# e407-roll-control.net
KiCad netlist of a schematic drawn in EAGLE
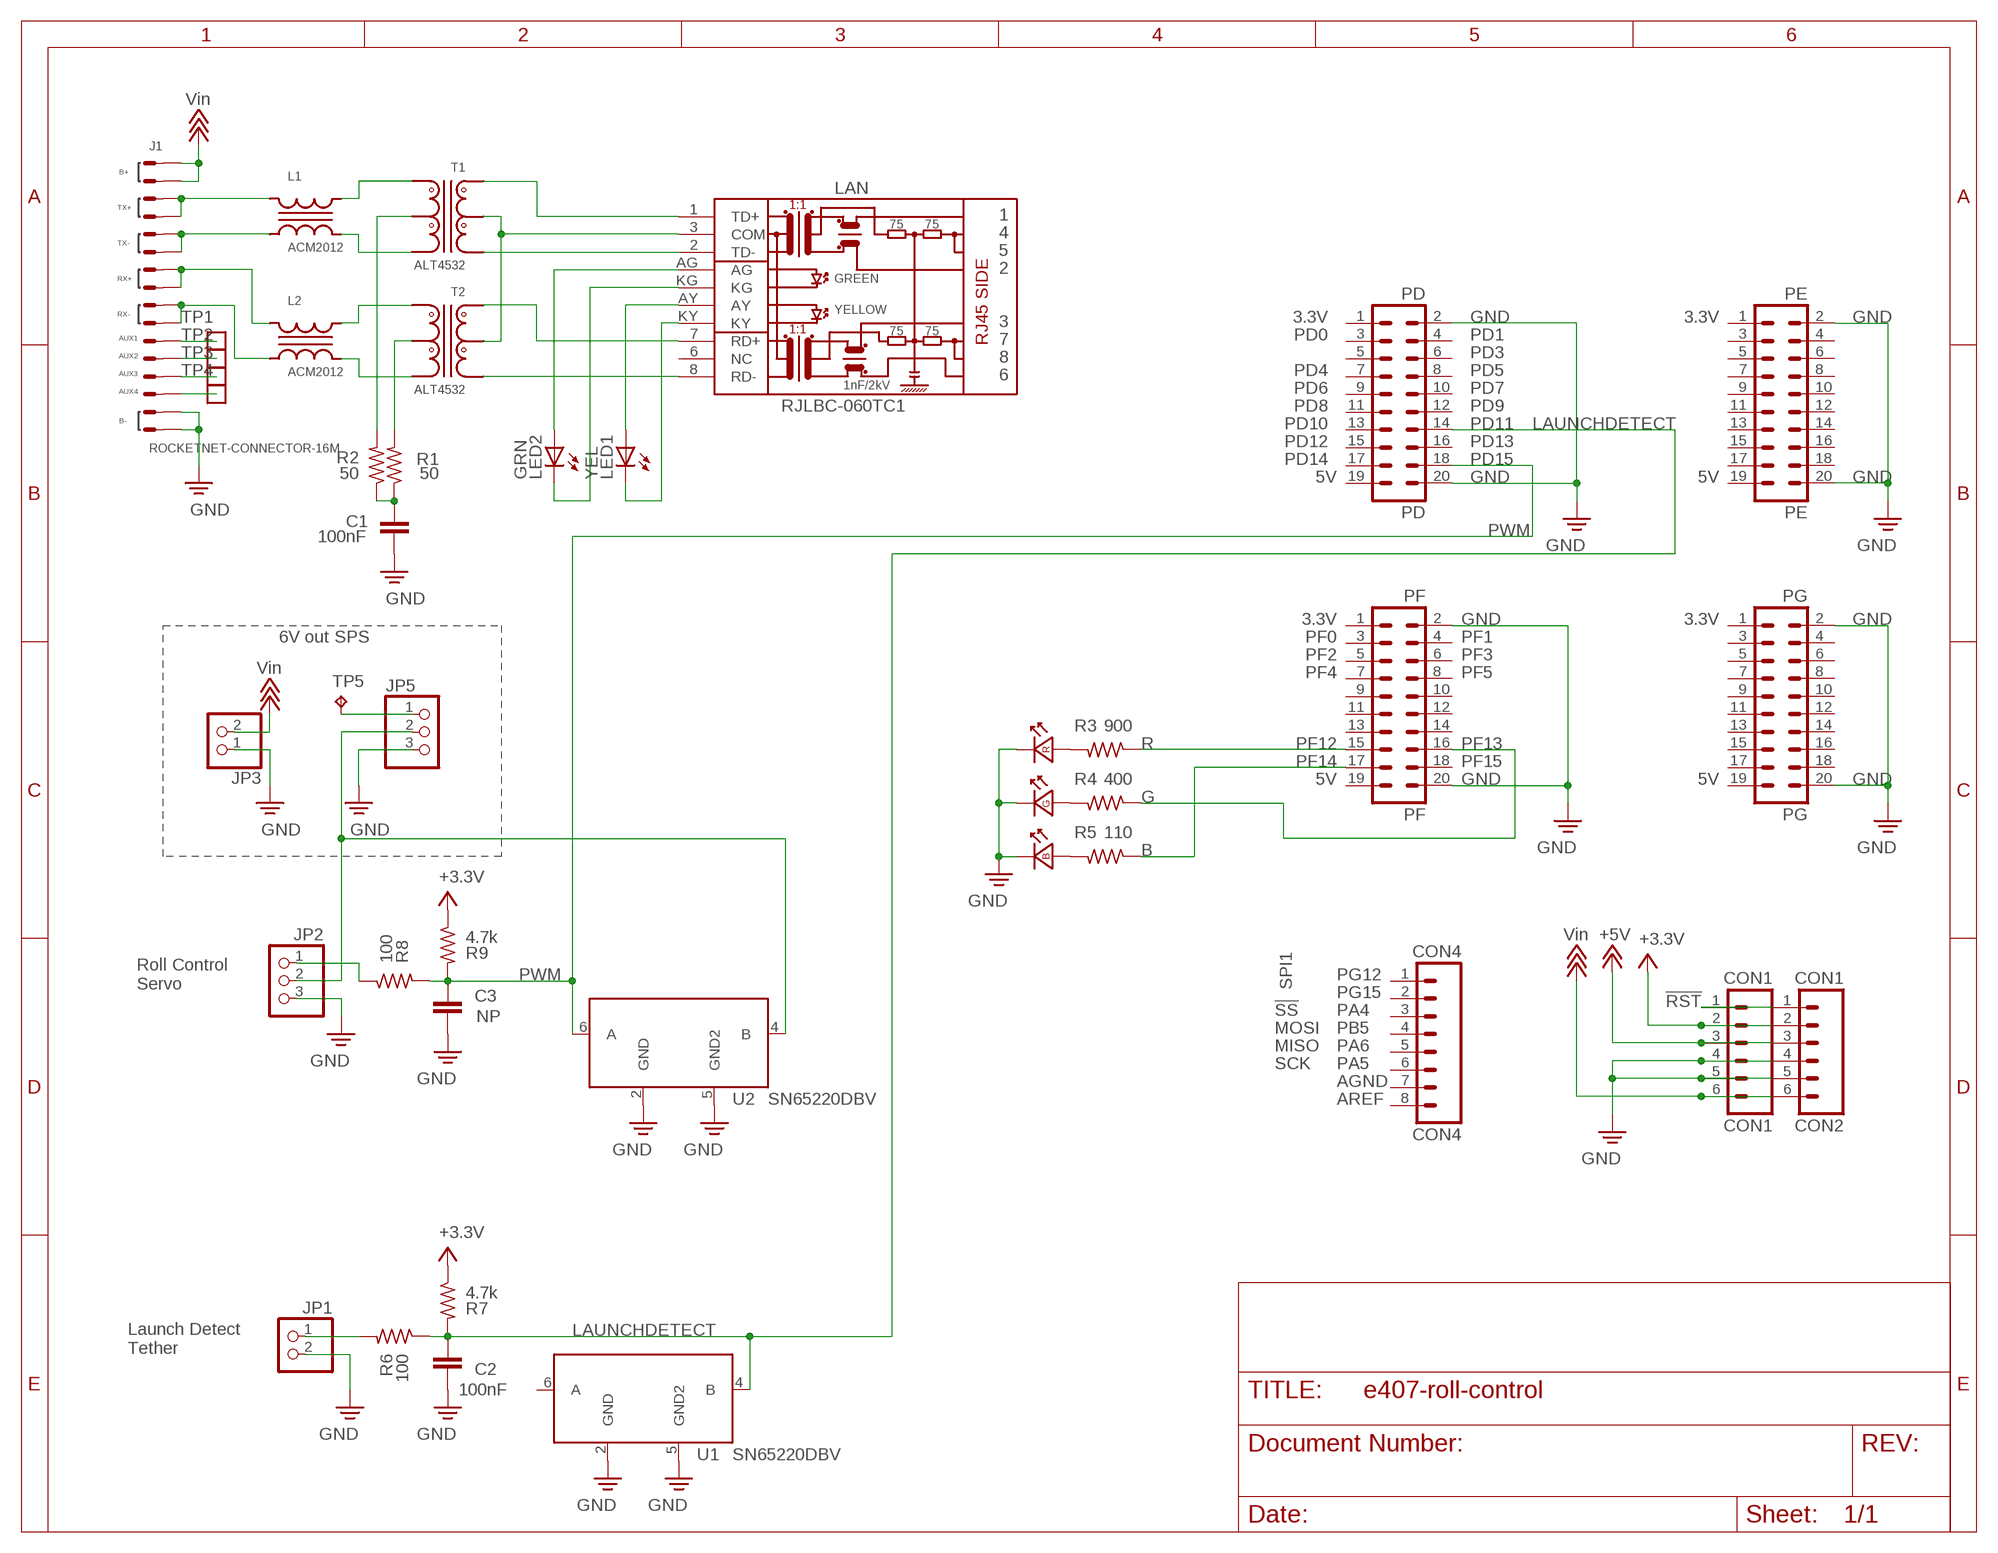
[diagram p0: schematic, sheet 1]

(export (version "E")
  (design (tool "Eeschema 10.0.6"))
  (components
    (comp (ref "C1")
      (value "100nF")
      (footprint "eagle-import:0603-B-NOSILK")
      (libsource (lib "eagle-import") (part "C-EU0603-B-NOSILK"))
    )
    (comp (ref "C2")
      (value "100nF")
      (footprint "eagle-import:0603-B-NOSILK")
      (libsource (lib "eagle-import") (part "C-EU0603-B-NOSILK"))
    )
    (comp (ref "C3")
      (value "NP")
      (footprint "eagle-import:0603-B-NOSILK")
      (libsource (lib "eagle-import") (part "C-EU0603-B-NOSILK"))
    )
    (comp (ref "CON1")
      (value "CON1")
      (footprint "eagle-import:1X06")
      (libsource (lib "eagle-import") (part "M06SIP"))
    )
    (comp (ref "CON2")
      (value "CON1")
      (footprint "eagle-import:1X06")
      (libsource (lib "eagle-import") (part "M06SIP"))
    )
    (comp (ref "CON4")
      (value "CON4")
      (footprint "eagle-import:1X08")
      (libsource (lib "eagle-import") (part "M081X08"))
    )
    (comp (ref "J1")
      (value "ROCKETNET-CONNECTOR-16M")
      (footprint "eagle-import:ROCKETNET-M-16")
      (libsource (lib "eagle-import") (part "ROCKETNET-CONNECTOR-16M"))
    )
    (comp (ref "JP1")
      (value "PINHD-1X2")
      (footprint "eagle-import:1X02")
      (libsource (lib "eagle-import") (part "PINHD-1X2"))
    )
    (comp (ref "JP2")
      (value "PINHD-1X3")
      (footprint "eagle-import:1X03")
      (libsource (lib "eagle-import") (part "PINHD-1X3"))
    )
    (comp (ref "JP3")
      (value "PINHD-1X2")
      (footprint "eagle-import:1X02")
      (libsource (lib "eagle-import") (part "PINHD-1X2"))
    )
    (comp (ref "JP5")
      (value "PINHD-1X3")
      (footprint "eagle-import:1X03")
      (libsource (lib "eagle-import") (part "PINHD-1X3"))
    )
    (comp (ref "L1")
      (value "ACM2012")
      (footprint "eagle-import:TDK-ACM2012")
      (libsource (lib "eagle-import") (part "ACM2012"))
    )
    (comp (ref "L2")
      (value "ACM2012")
      (footprint "eagle-import:TDK-ACM2012")
      (libsource (lib "eagle-import") (part "ACM2012"))
    )
    (comp (ref "LAN")
      (value "RJLBC-060TC1")
      (footprint "eagle-import:RJLBC-060TC1")
      (libsource (lib "eagle-import") (part "RJLBC-060TC1"))
    )
    (comp (ref "LED1")
      (value "YEL")
      (footprint "eagle-import:CHIPLED_0603")
      (libsource (lib "eagle-import") (part "LEDCHIPLED_0603"))
    )
    (comp (ref "LED2")
      (value "GRN")
      (footprint "eagle-import:CHIPLED_0603")
      (libsource (lib "eagle-import") (part "LEDCHIPLED_0603"))
    )
    (comp (ref "LED3")
      (value "LED_RGB_PLCC-6")
      (footprint "eagle-import:PLCC-6")
      (libsource (lib "eagle-import") (part "LED_RGB_PLCC-6"))
    )
    (comp (ref "PD")
      (value "PD")
      (footprint "eagle-import:ML20")
      (libsource (lib "eagle-import") (part "ML20"))
    )
    (comp (ref "PE")
      (value "PE")
      (footprint "eagle-import:ML20")
      (libsource (lib "eagle-import") (part "ML20"))
    )
    (comp (ref "PF")
      (value "PF")
      (footprint "eagle-import:ML20")
      (libsource (lib "eagle-import") (part "ML20"))
    )
    (comp (ref "PG")
      (value "PG")
      (footprint "eagle-import:ML20")
      (libsource (lib "eagle-import") (part "ML20"))
    )
    (comp (ref "R1")
      (value "50")
      (footprint "eagle-import:0603-B-NOSILK")
      (libsource (lib "eagle-import") (part "R-US_0603-B-NOSILK"))
    )
    (comp (ref "R2")
      (value "50")
      (footprint "eagle-import:0603-B-NOSILK")
      (libsource (lib "eagle-import") (part "R-US_0603-B-NOSILK"))
    )
    (comp (ref "R3")
      (value "900")
      (footprint "eagle-import:0603-B-NOSILK")
      (libsource (lib "eagle-import") (part "R-US_0603-B-NOSILK"))
    )
    (comp (ref "R4")
      (value "400")
      (footprint "eagle-import:0603-B-NOSILK")
      (libsource (lib "eagle-import") (part "R-US_0603-B-NOSILK"))
    )
    (comp (ref "R5")
      (value "110")
      (footprint "eagle-import:0603-B-NOSILK")
      (libsource (lib "eagle-import") (part "R-US_0603-B-NOSILK"))
    )
    (comp (ref "R6")
      (value "100")
      (footprint "eagle-import:0603-B-NOSILK")
      (libsource (lib "eagle-import") (part "R-US_0603-B-NOSILK"))
    )
    (comp (ref "R7")
      (value "4.7k")
      (footprint "eagle-import:0603-B-NOSILK")
      (libsource (lib "eagle-import") (part "R-US_0603-B-NOSILK"))
    )
    (comp (ref "R8")
      (value "100")
      (footprint "eagle-import:0603-B-NOSILK")
      (libsource (lib "eagle-import") (part "R-US_0603-B-NOSILK"))
    )
    (comp (ref "R9")
      (value "4.7k")
      (footprint "eagle-import:0603-B-NOSILK")
      (libsource (lib "eagle-import") (part "R-US_0603-B-NOSILK"))
    )
    (comp (ref "T1")
      (value "ALT4532")
      (footprint "eagle-import:TDK-ALT4532")
      (libsource (lib "eagle-import") (part "ALT4532"))
    )
    (comp (ref "T2")
      (value "ALT4532")
      (footprint "eagle-import:TDK-ALT4532")
      (libsource (lib "eagle-import") (part "ALT4532"))
    )
    (comp (ref "TP1")
      (value "TEST-POINT")
      (footprint "eagle-import:2MM-TEST-POINT")
      (libsource (lib "eagle-import") (part "TEST-POINT"))
    )
    (comp (ref "TP2")
      (value "TEST-POINT")
      (footprint "eagle-import:2MM-TEST-POINT")
      (libsource (lib "eagle-import") (part "TEST-POINT"))
    )
    (comp (ref "TP3")
      (value "TEST-POINT")
      (footprint "eagle-import:2MM-TEST-POINT")
      (libsource (lib "eagle-import") (part "TEST-POINT"))
    )
    (comp (ref "TP4")
      (value "TEST-POINT")
      (footprint "eagle-import:2MM-TEST-POINT")
      (libsource (lib "eagle-import") (part "TEST-POINT"))
    )
    (comp (ref "TP5")
      (value "TPPAD1-13")
      (footprint "eagle-import:P1-13")
      (libsource (lib "eagle-import") (part "TPPAD1-13"))
    )
    (comp (ref "U1")
      (value "SN65220DBV")
      (footprint "eagle-import:SOT23-6L")
      (libsource (lib "eagle-import") (part "SN65220DBV"))
    )
    (comp (ref "U2")
      (value "SN65220DBV")
      (footprint "eagle-import:SOT23-6L")
      (libsource (lib "eagle-import") (part "SN65220DBV"))
    )
  )
  (nets
    (net (code "1") (name "+3.3V") (class "Default")
      (node (ref "CON1") (pin "2") (pinfunction "2_2") (pintype "passive"))
      (node (ref "CON2") (pin "2") (pinfunction "2_2") (pintype "passive"))
      (node (ref "R7") (pin "1") (pinfunction "1_1") (pintype "passive"))
      (node (ref "R9") (pin "1") (pinfunction "1_1") (pintype "passive"))
    )
    (net (code "2") (name "+5V") (class "Default")
      (node (ref "CON1") (pin "3") (pinfunction "3_3") (pintype "passive"))
      (node (ref "CON2") (pin "3") (pinfunction "3_3") (pintype "passive"))
    )
    (net (code "3") (name "/B") (class "Default")
      (node (ref "PF") (pin "17") (pinfunction "17_17") (pintype "passive"))
      (node (ref "R5") (pin "1") (pinfunction "1_1") (pintype "passive"))
    )
    (net (code "4") (name "/G") (class "Default")
      (node (ref "PF") (pin "16") (pinfunction "16_16") (pintype "passive"))
      (node (ref "R4") (pin "1") (pinfunction "1_1") (pintype "passive"))
    )
    (net (code "5") (name "/LAUNCHDETECT") (class "Default")
      (node (ref "C2") (pin "2") (pinfunction "2_2") (pintype "passive"))
      (node (ref "PD") (pin "14") (pinfunction "14_14") (pintype "passive"))
      (node (ref "R6") (pin "1") (pinfunction "1_1") (pintype "passive"))
      (node (ref "R7") (pin "2") (pinfunction "2_2") (pintype "passive"))
      (node (ref "U1") (pin "4") (pinfunction "B_4") (pintype "passive"))
    )
    (net (code "6") (name "/PWM") (class "Default")
      (node (ref "C3") (pin "2") (pinfunction "2_2") (pintype "passive"))
      (node (ref "PD") (pin "18") (pinfunction "18_18") (pintype "passive"))
      (node (ref "R8") (pin "2") (pinfunction "2_2") (pintype "passive"))
      (node (ref "R9") (pin "2") (pinfunction "2_2") (pintype "passive"))
      (node (ref "U2") (pin "6") (pinfunction "A_6") (pintype "passive"))
    )
    (net (code "7") (name "/R") (class "Default")
      (node (ref "PF") (pin "15") (pinfunction "15_15") (pintype "passive"))
      (node (ref "R3") (pin "1") (pinfunction "1_1") (pintype "passive"))
    )
    (net (code "8") (name "GND") (class "Default")
      (node (ref "C1") (pin "2") (pinfunction "2_2") (pintype "passive"))
      (node (ref "C2") (pin "1") (pinfunction "1_1") (pintype "passive"))
      (node (ref "C3") (pin "1") (pinfunction "1_1") (pintype "passive"))
      (node (ref "CON1") (pin "4") (pinfunction "4_4") (pintype "passive"))
      (node (ref "CON1") (pin "5") (pinfunction "5_5") (pintype "passive"))
      (node (ref "CON2") (pin "4") (pinfunction "4_4") (pintype "passive"))
      (node (ref "CON2") (pin "5") (pinfunction "5_5") (pintype "passive"))
      (node (ref "J1") (pin "B-@1") (pinfunction "B-_B-@1") (pintype "power_in"))
      (node (ref "J1") (pin "B-@2") (pinfunction "B-_B-@2") (pintype "power_in"))
      (node (ref "JP1") (pin "2") (pinfunction "2_2") (pintype "passive"))
      (node (ref "JP2") (pin "3") (pinfunction "3_3") (pintype "passive"))
      (node (ref "JP3") (pin "1") (pinfunction "1_1") (pintype "passive"))
      (node (ref "JP5") (pin "3") (pinfunction "3_3") (pintype "passive"))
      (node (ref "LED3") (pin "2") (pinfunction "K_2") (pintype "passive"))
      (node (ref "LED3") (pin "5") (pinfunction "K_5") (pintype "passive"))
      (node (ref "LED3") (pin "6") (pinfunction "K_6") (pintype "passive"))
      (node (ref "PD") (pin "2") (pinfunction "2_2") (pintype "passive"))
      (node (ref "PD") (pin "20") (pinfunction "20_20") (pintype "passive"))
      (node (ref "PE") (pin "2") (pinfunction "2_2") (pintype "passive"))
      (node (ref "PE") (pin "20") (pinfunction "20_20") (pintype "passive"))
      (node (ref "PF") (pin "2") (pinfunction "2_2") (pintype "passive"))
      (node (ref "PF") (pin "20") (pinfunction "20_20") (pintype "passive"))
      (node (ref "PG") (pin "2") (pinfunction "2_2") (pintype "passive"))
      (node (ref "PG") (pin "20") (pinfunction "20_20") (pintype "passive"))
      (node (ref "U1") (pin "2") (pinfunction "GND_2") (pintype "power_in"))
      (node (ref "U1") (pin "5") (pinfunction "GND2_5") (pintype "power_in"))
      (node (ref "U2") (pin "2") (pinfunction "GND_2") (pintype "power_in"))
      (node (ref "U2") (pin "5") (pinfunction "GND2_5") (pintype "power_in"))
    )
    (net (code "9") (name "Net-(C1-Pad1)") (class "Default")
      (node (ref "C1") (pin "1") (pinfunction "1_1") (pintype "passive"))
      (node (ref "R1") (pin "1") (pinfunction "1_1") (pintype "passive"))
      (node (ref "R2") (pin "1") (pinfunction "1_1") (pintype "passive"))
    )
    (net (code "10") (name "Net-(CON1-Pad1)") (class "Default")
      (node (ref "CON1") (pin "1") (pinfunction "1_1") (pintype "passive"))
      (node (ref "CON2") (pin "1") (pinfunction "1_1") (pintype "passive"))
    )
    (net (code "11") (name "Net-(J1-AUX1)") (class "Default")
      (node (ref "J1") (pin "A1") (pinfunction "AUX1_A1") (pintype "passive"))
      (node (ref "TP1") (pin "1") (pinfunction "1_1") (pintype "passive"))
    )
    (net (code "12") (name "Net-(J1-AUX2)") (class "Default")
      (node (ref "J1") (pin "A2") (pinfunction "AUX2_A2") (pintype "passive"))
      (node (ref "TP2") (pin "1") (pinfunction "1_1") (pintype "passive"))
    )
    (net (code "13") (name "Net-(J1-AUX3)") (class "Default")
      (node (ref "J1") (pin "A3") (pinfunction "AUX3_A3") (pintype "passive"))
      (node (ref "TP3") (pin "1") (pinfunction "1_1") (pintype "passive"))
    )
    (net (code "14") (name "Net-(J1-AUX4)") (class "Default")
      (node (ref "J1") (pin "A4") (pinfunction "AUX4_A4") (pintype "passive"))
      (node (ref "TP4") (pin "1") (pinfunction "1_1") (pintype "passive"))
    )
    (net (code "15") (name "Net-(J1-RX+-PadR+@5)") (class "Default")
      (node (ref "J1") (pin "R+@5") (pinfunction "RX+_R+@5") (pintype "passive"))
      (node (ref "J1") (pin "R+@7") (pinfunction "RX+_R+@7") (pintype "passive"))
      (node (ref "L2") (pin "1") (pinfunction "1_1") (pintype "passive"))
    )
    (net (code "16") (name "Net-(J1-RX--PadR-@3)") (class "Default")
      (node (ref "J1") (pin "R-@3") (pinfunction "RX-_R-@3") (pintype "passive"))
      (node (ref "J1") (pin "R-@4") (pinfunction "RX-_R-@4") (pintype "passive"))
      (node (ref "L2") (pin "2") (pinfunction "2_2") (pintype "passive"))
    )
    (net (code "17") (name "Net-(J1-TX+-PadT+@13)") (class "Default")
      (node (ref "J1") (pin "T+@13") (pinfunction "TX+_T+@13") (pintype "passive"))
      (node (ref "J1") (pin "T+@14") (pinfunction "TX+_T+@14") (pintype "passive"))
      (node (ref "L1") (pin "1") (pinfunction "1_1") (pintype "passive"))
    )
    (net (code "18") (name "Net-(J1-TX--PadT-@11)") (class "Default")
      (node (ref "J1") (pin "T-@11") (pinfunction "TX-_T-@11") (pintype "passive"))
      (node (ref "J1") (pin "T-@9") (pinfunction "TX-_T-@9") (pintype "passive"))
      (node (ref "L1") (pin "2") (pinfunction "2_2") (pintype "passive"))
    )
    (net (code "19") (name "Net-(JP1-Pad1)") (class "Default")
      (node (ref "JP1") (pin "1") (pinfunction "1_1") (pintype "passive"))
      (node (ref "R6") (pin "2") (pinfunction "2_2") (pintype "passive"))
    )
    (net (code "20") (name "Net-(JP2-Pad1)") (class "Default")
      (node (ref "JP2") (pin "1") (pinfunction "1_1") (pintype "passive"))
      (node (ref "R8") (pin "1") (pinfunction "1_1") (pintype "passive"))
    )
    (net (code "21") (name "Net-(JP5-Pad1)") (class "Default")
      (node (ref "JP5") (pin "1") (pinfunction "1_1") (pintype "passive"))
      (node (ref "TP5") (pin "TP") (pinfunction "TP_TP") (pintype "input"))
    )
    (net (code "22") (name "Net-(L1-Pad3)") (class "Default")
      (node (ref "L1") (pin "3") (pinfunction "3_3") (pintype "passive"))
      (node (ref "T1") (pin "4") (pinfunction "4_4") (pintype "passive"))
    )
    (net (code "23") (name "Net-(L1-Pad4)") (class "Default")
      (node (ref "L1") (pin "4") (pinfunction "4_4") (pintype "passive"))
      (node (ref "T1") (pin "5") (pinfunction "5_5") (pintype "passive"))
    )
    (net (code "24") (name "Net-(L2-Pad3)") (class "Default")
      (node (ref "L2") (pin "3") (pinfunction "3_3") (pintype "passive"))
      (node (ref "T2") (pin "4") (pinfunction "4_4") (pintype "passive"))
    )
    (net (code "25") (name "Net-(L2-Pad4)") (class "Default")
      (node (ref "L2") (pin "4") (pinfunction "4_4") (pintype "passive"))
      (node (ref "T2") (pin "5") (pinfunction "5_5") (pintype "passive"))
    )
    (net (code "26") (name "Net-(LAN-COM)") (class "Default")
      (node (ref "LAN") (pin "3") (pinfunction "COM_3") (pintype "bidirectional"))
      (node (ref "T1") (pin "6") (pinfunction "6_6") (pintype "passive"))
      (node (ref "T2") (pin "6") (pinfunction "6_6") (pintype "passive"))
    )
    (net (code "27") (name "Net-(LAN-PadAG)") (class "Default")
      (node (ref "LAN") (pin "AG") (pinfunction "AG_AG") (pintype "passive"))
      (node (ref "LED2") (pin "A") (pinfunction "A_A") (pintype "passive"))
    )
    (net (code "28") (name "Net-(LAN-PadAY)") (class "Default")
      (node (ref "LAN") (pin "AY") (pinfunction "AY_AY") (pintype "passive"))
      (node (ref "LED1") (pin "A") (pinfunction "A_A") (pintype "passive"))
    )
    (net (code "29") (name "Net-(LAN-PadKG)") (class "Default")
      (node (ref "LAN") (pin "KG") (pinfunction "KG_KG") (pintype "passive"))
      (node (ref "LED2") (pin "C") (pinfunction "C_C") (pintype "passive"))
    )
    (net (code "30") (name "Net-(LAN-PadKY)") (class "Default")
      (node (ref "LAN") (pin "KY") (pinfunction "KY_KY") (pintype "passive"))
      (node (ref "LED1") (pin "C") (pinfunction "C_C") (pintype "passive"))
    )
    (net (code "31") (name "Net-(LAN-RD+)") (class "Default")
      (node (ref "LAN") (pin "7") (pinfunction "RD+_7") (pintype "bidirectional"))
      (node (ref "T2") (pin "1") (pinfunction "1_1") (pintype "passive"))
    )
    (net (code "32") (name "Net-(LAN-RD-)") (class "Default")
      (node (ref "LAN") (pin "8") (pinfunction "RD-_8") (pintype "bidirectional"))
      (node (ref "T2") (pin "2") (pinfunction "2_2") (pintype "passive"))
    )
    (net (code "33") (name "Net-(LAN-TD+)") (class "Default")
      (node (ref "LAN") (pin "1") (pinfunction "TD+_1") (pintype "bidirectional"))
      (node (ref "T1") (pin "1") (pinfunction "1_1") (pintype "passive"))
    )
    (net (code "34") (name "Net-(LAN-TD-)") (class "Default")
      (node (ref "LAN") (pin "2") (pinfunction "TD-_2") (pintype "bidirectional"))
      (node (ref "T1") (pin "2") (pinfunction "2_2") (pintype "passive"))
    )
    (net (code "35") (name "Net-(LED3A-A)") (class "Default")
      (node (ref "LED3") (pin "4") (pinfunction "A_4") (pintype "passive"))
      (node (ref "R5") (pin "2") (pinfunction "2_2") (pintype "passive"))
    )
    (net (code "36") (name "Net-(LED3B-A)") (class "Default")
      (node (ref "LED3") (pin "3") (pinfunction "A_3") (pintype "passive"))
      (node (ref "R4") (pin "2") (pinfunction "2_2") (pintype "passive"))
    )
    (net (code "37") (name "Net-(LED3D-A)") (class "Default")
      (node (ref "LED3") (pin "1") (pinfunction "A_1") (pintype "passive"))
      (node (ref "R3") (pin "2") (pinfunction "2_2") (pintype "passive"))
    )
    (net (code "38") (name "Net-(R1-Pad2)") (class "Default")
      (node (ref "R1") (pin "2") (pinfunction "2_2") (pintype "passive"))
      (node (ref "T2") (pin "3") (pinfunction "3_3") (pintype "passive"))
    )
    (net (code "39") (name "Net-(R2-Pad2)") (class "Default")
      (node (ref "R2") (pin "2") (pinfunction "2_2") (pintype "passive"))
      (node (ref "T1") (pin "3") (pinfunction "3_3") (pintype "passive"))
    )
    (net (code "40") (name "Net-(U2-B)") (class "Default")
      (node (ref "JP2") (pin "2") (pinfunction "2_2") (pintype "passive"))
      (node (ref "JP5") (pin "2") (pinfunction "2_2") (pintype "passive"))
      (node (ref "U2") (pin "4") (pinfunction "B_4") (pintype "passive"))
    )
    (net (code "41") (name "Vin") (class "Default")
      (node (ref "CON1") (pin "6") (pinfunction "6_6") (pintype "passive"))
      (node (ref "CON2") (pin "6") (pinfunction "6_6") (pintype "passive"))
      (node (ref "J1") (pin "B+@15") (pinfunction "B+_B+@15") (pintype "power_in"))
      (node (ref "J1") (pin "B+@16") (pinfunction "B+_B+@16") (pintype "power_in"))
      (node (ref "JP3") (pin "2") (pinfunction "2_2") (pintype "passive"))
    )
    (net (code "42") (name "unconnected-(CON4-Pad1)") (class "Default")
      (node (ref "CON4") (pin "1") (pinfunction "1_1") (pintype "passive"))
    )
    (net (code "43") (name "unconnected-(CON4-Pad2)") (class "Default")
      (node (ref "CON4") (pin "2") (pinfunction "2_2") (pintype "passive"))
    )
    (net (code "44") (name "unconnected-(CON4-Pad3)") (class "Default")
      (node (ref "CON4") (pin "3") (pinfunction "3_3") (pintype "passive"))
    )
    (net (code "45") (name "unconnected-(CON4-Pad4)") (class "Default")
      (node (ref "CON4") (pin "4") (pinfunction "4_4") (pintype "passive"))
    )
    (net (code "46") (name "unconnected-(CON4-Pad5)") (class "Default")
      (node (ref "CON4") (pin "5") (pinfunction "5_5") (pintype "passive"))
    )
    (net (code "47") (name "unconnected-(CON4-Pad6)") (class "Default")
      (node (ref "CON4") (pin "6") (pinfunction "6_6") (pintype "passive"))
    )
    (net (code "48") (name "unconnected-(CON4-Pad7)") (class "Default")
      (node (ref "CON4") (pin "7") (pinfunction "7_7") (pintype "passive"))
    )
    (net (code "49") (name "unconnected-(CON4-Pad8)") (class "Default")
      (node (ref "CON4") (pin "8") (pinfunction "8_8") (pintype "passive"))
    )
    (net (code "50") (name "unconnected-(LAN-NC-Pad6)") (class "Default")
      (node (ref "LAN") (pin "6") (pinfunction "NC_6") (pintype "bidirectional"))
    )
    (net (code "51") (name "unconnected-(PD-Pad1)") (class "Default")
      (node (ref "PD") (pin "1") (pinfunction "1_1") (pintype "passive"))
    )
    (net (code "52") (name "unconnected-(PD-Pad3)") (class "Default")
      (node (ref "PD") (pin "3") (pinfunction "3_3") (pintype "passive"))
    )
    (net (code "53") (name "unconnected-(PD-Pad4)") (class "Default")
      (node (ref "PD") (pin "4") (pinfunction "4_4") (pintype "passive"))
    )
    (net (code "54") (name "unconnected-(PD-Pad5)") (class "Default")
      (node (ref "PD") (pin "5") (pinfunction "5_5") (pintype "passive"))
    )
    (net (code "55") (name "unconnected-(PD-Pad6)") (class "Default")
      (node (ref "PD") (pin "6") (pinfunction "6_6") (pintype "passive"))
    )
    (net (code "56") (name "unconnected-(PD-Pad7)") (class "Default")
      (node (ref "PD") (pin "7") (pinfunction "7_7") (pintype "passive"))
    )
    (net (code "57") (name "unconnected-(PD-Pad8)") (class "Default")
      (node (ref "PD") (pin "8") (pinfunction "8_8") (pintype "passive"))
    )
    (net (code "58") (name "unconnected-(PD-Pad9)") (class "Default")
      (node (ref "PD") (pin "9") (pinfunction "9_9") (pintype "passive"))
    )
    (net (code "59") (name "unconnected-(PD-Pad10)") (class "Default")
      (node (ref "PD") (pin "10") (pinfunction "10_10") (pintype "passive"))
    )
    (net (code "60") (name "unconnected-(PD-Pad11)") (class "Default")
      (node (ref "PD") (pin "11") (pinfunction "11_11") (pintype "passive"))
    )
    (net (code "61") (name "unconnected-(PD-Pad12)") (class "Default")
      (node (ref "PD") (pin "12") (pinfunction "12_12") (pintype "passive"))
    )
    (net (code "62") (name "unconnected-(PD-Pad13)") (class "Default")
      (node (ref "PD") (pin "13") (pinfunction "13_13") (pintype "passive"))
    )
    (net (code "63") (name "unconnected-(PD-Pad15)") (class "Default")
      (node (ref "PD") (pin "15") (pinfunction "15_15") (pintype "passive"))
    )
    (net (code "64") (name "unconnected-(PD-Pad16)") (class "Default")
      (node (ref "PD") (pin "16") (pinfunction "16_16") (pintype "passive"))
    )
    (net (code "65") (name "unconnected-(PD-Pad17)") (class "Default")
      (node (ref "PD") (pin "17") (pinfunction "17_17") (pintype "passive"))
    )
    (net (code "66") (name "unconnected-(PD-Pad19)") (class "Default")
      (node (ref "PD") (pin "19") (pinfunction "19_19") (pintype "passive"))
    )
    (net (code "67") (name "unconnected-(PE-Pad1)") (class "Default")
      (node (ref "PE") (pin "1") (pinfunction "1_1") (pintype "passive"))
    )
    (net (code "68") (name "unconnected-(PE-Pad3)") (class "Default")
      (node (ref "PE") (pin "3") (pinfunction "3_3") (pintype "passive"))
    )
    (net (code "69") (name "unconnected-(PE-Pad4)") (class "Default")
      (node (ref "PE") (pin "4") (pinfunction "4_4") (pintype "passive"))
    )
    (net (code "70") (name "unconnected-(PE-Pad5)") (class "Default")
      (node (ref "PE") (pin "5") (pinfunction "5_5") (pintype "passive"))
    )
    (net (code "71") (name "unconnected-(PE-Pad6)") (class "Default")
      (node (ref "PE") (pin "6") (pinfunction "6_6") (pintype "passive"))
    )
    (net (code "72") (name "unconnected-(PE-Pad7)") (class "Default")
      (node (ref "PE") (pin "7") (pinfunction "7_7") (pintype "passive"))
    )
    (net (code "73") (name "unconnected-(PE-Pad8)") (class "Default")
      (node (ref "PE") (pin "8") (pinfunction "8_8") (pintype "passive"))
    )
    (net (code "74") (name "unconnected-(PE-Pad9)") (class "Default")
      (node (ref "PE") (pin "9") (pinfunction "9_9") (pintype "passive"))
    )
    (net (code "75") (name "unconnected-(PE-Pad10)") (class "Default")
      (node (ref "PE") (pin "10") (pinfunction "10_10") (pintype "passive"))
    )
    (net (code "76") (name "unconnected-(PE-Pad11)") (class "Default")
      (node (ref "PE") (pin "11") (pinfunction "11_11") (pintype "passive"))
    )
    (net (code "77") (name "unconnected-(PE-Pad12)") (class "Default")
      (node (ref "PE") (pin "12") (pinfunction "12_12") (pintype "passive"))
    )
    (net (code "78") (name "unconnected-(PE-Pad13)") (class "Default")
      (node (ref "PE") (pin "13") (pinfunction "13_13") (pintype "passive"))
    )
    (net (code "79") (name "unconnected-(PE-Pad14)") (class "Default")
      (node (ref "PE") (pin "14") (pinfunction "14_14") (pintype "passive"))
    )
    (net (code "80") (name "unconnected-(PE-Pad15)") (class "Default")
      (node (ref "PE") (pin "15") (pinfunction "15_15") (pintype "passive"))
    )
    (net (code "81") (name "unconnected-(PE-Pad16)") (class "Default")
      (node (ref "PE") (pin "16") (pinfunction "16_16") (pintype "passive"))
    )
    (net (code "82") (name "unconnected-(PE-Pad17)") (class "Default")
      (node (ref "PE") (pin "17") (pinfunction "17_17") (pintype "passive"))
    )
    (net (code "83") (name "unconnected-(PE-Pad18)") (class "Default")
      (node (ref "PE") (pin "18") (pinfunction "18_18") (pintype "passive"))
    )
    (net (code "84") (name "unconnected-(PE-Pad19)") (class "Default")
      (node (ref "PE") (pin "19") (pinfunction "19_19") (pintype "passive"))
    )
    (net (code "85") (name "unconnected-(PF-Pad1)") (class "Default")
      (node (ref "PF") (pin "1") (pinfunction "1_1") (pintype "passive"))
    )
    (net (code "86") (name "unconnected-(PF-Pad3)") (class "Default")
      (node (ref "PF") (pin "3") (pinfunction "3_3") (pintype "passive"))
    )
    (net (code "87") (name "unconnected-(PF-Pad4)") (class "Default")
      (node (ref "PF") (pin "4") (pinfunction "4_4") (pintype "passive"))
    )
    (net (code "88") (name "unconnected-(PF-Pad5)") (class "Default")
      (node (ref "PF") (pin "5") (pinfunction "5_5") (pintype "passive"))
    )
    (net (code "89") (name "unconnected-(PF-Pad6)") (class "Default")
      (node (ref "PF") (pin "6") (pinfunction "6_6") (pintype "passive"))
    )
    (net (code "90") (name "unconnected-(PF-Pad7)") (class "Default")
      (node (ref "PF") (pin "7") (pinfunction "7_7") (pintype "passive"))
    )
    (net (code "91") (name "unconnected-(PF-Pad8)") (class "Default")
      (node (ref "PF") (pin "8") (pinfunction "8_8") (pintype "passive"))
    )
    (net (code "92") (name "unconnected-(PF-Pad9)") (class "Default")
      (node (ref "PF") (pin "9") (pinfunction "9_9") (pintype "passive"))
    )
    (net (code "93") (name "unconnected-(PF-Pad10)") (class "Default")
      (node (ref "PF") (pin "10") (pinfunction "10_10") (pintype "passive"))
    )
    (net (code "94") (name "unconnected-(PF-Pad11)") (class "Default")
      (node (ref "PF") (pin "11") (pinfunction "11_11") (pintype "passive"))
    )
    (net (code "95") (name "unconnected-(PF-Pad12)") (class "Default")
      (node (ref "PF") (pin "12") (pinfunction "12_12") (pintype "passive"))
    )
    (net (code "96") (name "unconnected-(PF-Pad13)") (class "Default")
      (node (ref "PF") (pin "13") (pinfunction "13_13") (pintype "passive"))
    )
    (net (code "97") (name "unconnected-(PF-Pad14)") (class "Default")
      (node (ref "PF") (pin "14") (pinfunction "14_14") (pintype "passive"))
    )
    (net (code "98") (name "unconnected-(PF-Pad18)") (class "Default")
      (node (ref "PF") (pin "18") (pinfunction "18_18") (pintype "passive"))
    )
    (net (code "99") (name "unconnected-(PF-Pad19)") (class "Default")
      (node (ref "PF") (pin "19") (pinfunction "19_19") (pintype "passive"))
    )
    (net (code "100") (name "unconnected-(PG-Pad1)") (class "Default")
      (node (ref "PG") (pin "1") (pinfunction "1_1") (pintype "passive"))
    )
    (net (code "101") (name "unconnected-(PG-Pad3)") (class "Default")
      (node (ref "PG") (pin "3") (pinfunction "3_3") (pintype "passive"))
    )
    (net (code "102") (name "unconnected-(PG-Pad4)") (class "Default")
      (node (ref "PG") (pin "4") (pinfunction "4_4") (pintype "passive"))
    )
    (net (code "103") (name "unconnected-(PG-Pad5)") (class "Default")
      (node (ref "PG") (pin "5") (pinfunction "5_5") (pintype "passive"))
    )
    (net (code "104") (name "unconnected-(PG-Pad6)") (class "Default")
      (node (ref "PG") (pin "6") (pinfunction "6_6") (pintype "passive"))
    )
    (net (code "105") (name "unconnected-(PG-Pad7)") (class "Default")
      (node (ref "PG") (pin "7") (pinfunction "7_7") (pintype "passive"))
    )
    (net (code "106") (name "unconnected-(PG-Pad8)") (class "Default")
      (node (ref "PG") (pin "8") (pinfunction "8_8") (pintype "passive"))
    )
    (net (code "107") (name "unconnected-(PG-Pad9)") (class "Default")
      (node (ref "PG") (pin "9") (pinfunction "9_9") (pintype "passive"))
    )
    (net (code "108") (name "unconnected-(PG-Pad10)") (class "Default")
      (node (ref "PG") (pin "10") (pinfunction "10_10") (pintype "passive"))
    )
    (net (code "109") (name "unconnected-(PG-Pad11)") (class "Default")
      (node (ref "PG") (pin "11") (pinfunction "11_11") (pintype "passive"))
    )
    (net (code "110") (name "unconnected-(PG-Pad12)") (class "Default")
      (node (ref "PG") (pin "12") (pinfunction "12_12") (pintype "passive"))
    )
    (net (code "111") (name "unconnected-(PG-Pad13)") (class "Default")
      (node (ref "PG") (pin "13") (pinfunction "13_13") (pintype "passive"))
    )
    (net (code "112") (name "unconnected-(PG-Pad14)") (class "Default")
      (node (ref "PG") (pin "14") (pinfunction "14_14") (pintype "passive"))
    )
    (net (code "113") (name "unconnected-(PG-Pad15)") (class "Default")
      (node (ref "PG") (pin "15") (pinfunction "15_15") (pintype "passive"))
    )
    (net (code "114") (name "unconnected-(PG-Pad16)") (class "Default")
      (node (ref "PG") (pin "16") (pinfunction "16_16") (pintype "passive"))
    )
    (net (code "115") (name "unconnected-(PG-Pad17)") (class "Default")
      (node (ref "PG") (pin "17") (pinfunction "17_17") (pintype "passive"))
    )
    (net (code "116") (name "unconnected-(PG-Pad18)") (class "Default")
      (node (ref "PG") (pin "18") (pinfunction "18_18") (pintype "passive"))
    )
    (net (code "117") (name "unconnected-(PG-Pad19)") (class "Default")
      (node (ref "PG") (pin "19") (pinfunction "19_19") (pintype "passive"))
    )
    (net (code "118") (name "unconnected-(U1-A-Pad6)") (class "Default")
      (node (ref "U1") (pin "6") (pinfunction "A_6") (pintype "passive"))
    )
  )
)
